# STM32.net
KiCad netlist of a schematic drawn in Altium Designer
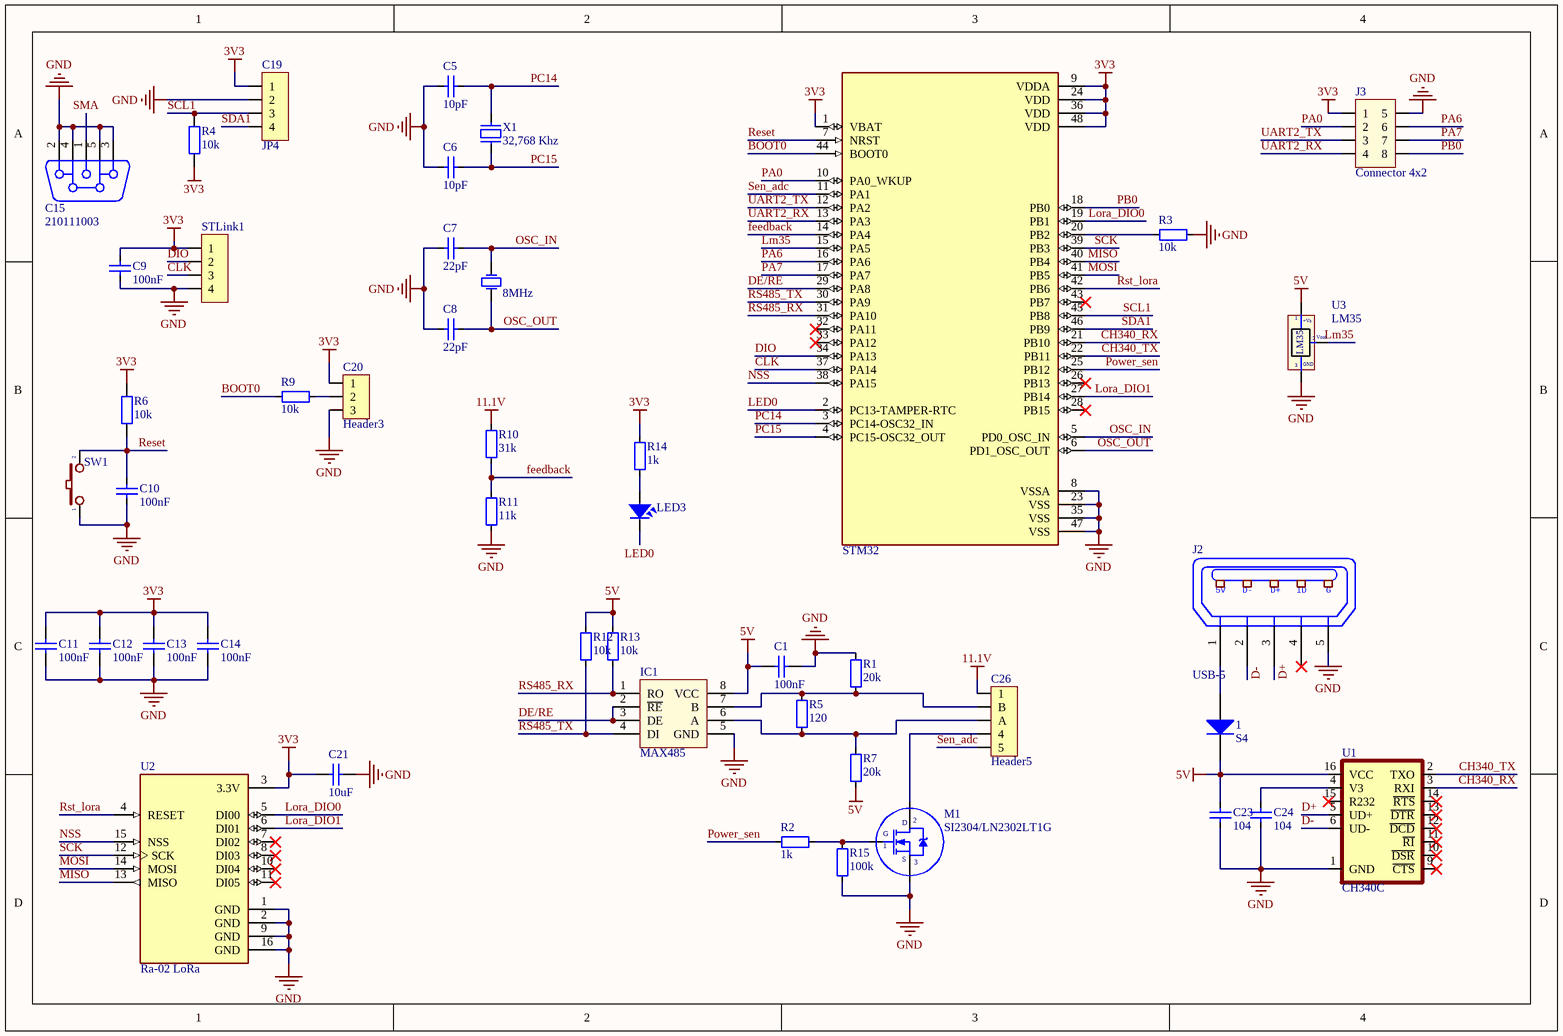
[diagram p0: STM32.SchDoc]

(export (version "E")
  (design (tool "Eeschema 10.0.6"))
  (components
    (comp (ref "1")
      (value "S4")
      (footprint "DIO-214AC(SMA)")
      (description "Dán")
      (libsource (lib "THU VIEN SCH") (part "Diode S4"))
    )
    (comp (ref "C1")
      (value "100nF")
      (footprint "CAP_0805")
      (description "Capacitor")
      (fields (field (name "PUBLISHER") "Altium Limited"))
      (libsource (lib "") (part "CapSMD_1"))
    )
    (comp (ref "C5")
      (value "10pF")
      (footprint "CAP_0805")
      (description "Capacitor")
      (fields (field (name "PUBLISHER") "Altium Limited"))
      (libsource (lib "My Library") (part "CapSMD"))
    )
    (comp (ref "C6")
      (value "10pF")
      (footprint "CAP_0805")
      (description "Capacitor")
      (fields (field (name "PUBLISHER") "Altium Limited"))
      (libsource (lib "My Library") (part "CapSMD"))
    )
    (comp (ref "C7")
      (value "22pF")
      (footprint "CAP_0805")
      (description "Capacitor")
      (fields (field (name "PUBLISHER") "Altium Limited"))
      (libsource (lib "My Library") (part "CapSMD"))
    )
    (comp (ref "C8")
      (value "22pF")
      (footprint "CAP_0805")
      (description "Capacitor")
      (fields (field (name "PUBLISHER") "Altium Limited"))
      (libsource (lib "My Library") (part "CapSMD"))
    )
    (comp (ref "C9")
      (value "100nF")
      (footprint "CAP_0805")
      (description "Capacitor")
      (fields (field (name "PUBLISHER") "Altium Limited"))
      (libsource (lib "My Library") (part "CapSMD"))
    )
    (comp (ref "C10")
      (value "100nF")
      (footprint "CAP_0805")
      (description "Capacitor")
      (fields (field (name "PUBLISHER") "Altium Limited"))
      (libsource (lib "My Library") (part "CapSMD"))
    )
    (comp (ref "C11")
      (value "100nF")
      (footprint "CAP_0805")
      (description "Capacitor")
      (fields (field (name "PUBLISHER") "Altium Limited"))
      (libsource (lib "") (part "CapSMD_1"))
    )
    (comp (ref "C12")
      (value "100nF")
      (footprint "CAP_0805")
      (description "Capacitor")
      (fields (field (name "PUBLISHER") "Altium Limited"))
      (libsource (lib "") (part "CapSMD_1"))
    )
    (comp (ref "C13")
      (value "100nF")
      (footprint "CAP_0805")
      (description "Capacitor")
      (fields (field (name "PUBLISHER") "Altium Limited"))
      (libsource (lib "") (part "CapSMD_1"))
    )
    (comp (ref "C14")
      (value "100nF")
      (footprint "CAP_0805")
      (description "Capacitor")
      (fields (field (name "PUBLISHER") "Altium Limited"))
      (libsource (lib "") (part "CapSMD_1"))
    )
    (comp (ref "C15")
      (value "210111003")
      (footprint "SMA-RA")
      (description "CONNECTOR ANTEN")
      (fields
        (field (name "MANUFACTURER") "Würth Elektronik eiSos GmbH")
        (field (name "CREATED BY") "Christin Zierenner")
      )
      (libsource (lib "My Library") (part "CON Ant"))
    )
    (comp (ref "C19")
      (value "JP4")
      (footprint "JP4-C1T")
      (description "WR-PHD 2.54 mm Angled Socket Header")
      (fields
        (field (name "MANUFACTURER") "Würth Elektronik eiSos GmbH")
        (field (name "PARTNO") "613004143121")
        (field (name "CREATED BY") "Karrer Zheng")
      )
      (libsource (lib "My Library") (part "JP4"))
    )
    (comp (ref "C20")
      (value "Header3")
      (footprint "JP3")
      (description "Header IDC, 3 x 1 Pin Vertical 2.54mm Pitch (Non-Boxed, Male)")
      (fields
        (field (name "MANUFACTURER") "Würth Elektronik eiSos GmbH")
        (field (name "PARTNO") "613002143121")
        (field (name "CREATED BY") "Karrer Zheng")
      )
      (libsource (lib "My Library") (part "Header3"))
    )
    (comp (ref "C21")
      (value "10uF")
      (footprint "CAP_0805")
      (description "Capacitor")
      (fields (field (name "PUBLISHER") "Altium Limited"))
      (libsource (lib "") (part "CapSMD_1"))
    )
    (comp (ref "C23")
      (value "104")
      (footprint "CAP_0805")
      (description "Capacitor")
      (fields (field (name "PUBLISHER") "Altium Limited"))
      (libsource (lib "My Library") (part "CapSMD"))
    )
    (comp (ref "C24")
      (value "104")
      (footprint "CAP_0805")
      (description "Capacitor")
      (fields (field (name "PUBLISHER") "Altium Limited"))
      (libsource (lib "My Library") (part "CapSMD"))
    )
    (comp (ref "C26")
      (value "Header5")
      (footprint "KF5-5")
      (description "Header IDC, 5 x 1 Pin Vertical 2.54mm Pitch (Non-Boxed, Male)")
      (fields
        (field (name "MANUFACTURER") "Würth Elektronik eiSos GmbH")
        (field (name "PARTNO") "613002143121")
        (field (name "CREATED BY") "Karrer Zheng")
      )
      (libsource (lib "My Library") (part "Header5"))
    )
    (comp (ref "IC1")
      (value "MAX485")
      (footprint "SO-8")
      (description "RS232 - RS485 (Same sn75176)")
      (libsource (lib "My Library") (part "MAX485"))
    )
    (comp (ref "J2")
      (value "USB-5")
      (footprint "USB-M1")
      (fields
        (field (name "MANUFACTURER") "FCI")
        (field (name "MANUFACTURER PART NUMBER") "10118193-0001LF")
        (field (name ".CREATOR") "MM")
        (field (name ".CHECKED PCB") "RF")
        (field (name ".CHECKED SCH") "MM")
      )
      (libsource (lib "My Library") (part "USB-5"))
    )
    (comp (ref "J3")
      (value "Connector 4x2")
      (footprint "JP4x2")
      (libsource (lib "My Library") (part "JP4x2"))
    )
    (comp (ref "LED3")
      (value "LED")
      (footprint "LED-0805-Blue")
      (description "LED Single colour Green and Red")
      (libsource (lib "My Library") (part "LED"))
    )
    (comp (ref "M1")
      (value "SI2304/LN2302LT1G")
      (footprint "SOT23A")
      (description "Generic N Channel MOSFET")
      (libsource (lib "My Library") (part "MOSFET_N"))
    )
    (comp (ref "R1")
      (value "20k")
      (footprint "RES-SMD-0805")
      (description "Resistor")
      (fields
        (field (name "MANUFACTURER") "Generic Components")
        (field (name "PUBLISHER") "Altium Hobart Technology Centre")
      )
      (libsource (lib "My Library") (part "Resistor - SMD"))
    )
    (comp (ref "R2")
      (value "1k")
      (footprint "RES-SMD-0805")
      (description "Resistor")
      (fields
        (field (name "MANUFACTURER") "Generic Components")
        (field (name "PUBLISHER") "Altium Hobart Technology Centre")
      )
      (libsource (lib "My Library") (part "Resistor - SMD"))
    )
    (comp (ref "R3")
      (value "10k")
      (footprint "RES-SMD-0805")
      (description "Resistor")
      (fields
        (field (name "MANUFACTURER") "Generic Components")
        (field (name "PUBLISHER") "Altium Hobart Technology Centre")
      )
      (libsource (lib "My Library") (part "Resistor - SMD"))
    )
    (comp (ref "R4")
      (value "10k")
      (footprint "RES_SMD_0805")
      (description "Resistor SMD")
      (fields
        (field (name "MANUFACTURER") "Generic Components")
        (field (name "PUBLISHER") "Altium Hobart Technology Centre")
      )
      (libsource (lib "") (part "Resistor - SMD_1"))
    )
    (comp (ref "R5")
      (value "120")
      (footprint "RES-SMD-0805")
      (description "Resistor")
      (fields
        (field (name "MANUFACTURER") "Generic Components")
        (field (name "PUBLISHER") "Altium Hobart Technology Centre")
      )
      (libsource (lib "My Library") (part "Resistor - SMD"))
    )
    (comp (ref "R6")
      (value "10k")
      (footprint "RES_SMD_0805")
      (description "Resistor SMD")
      (fields
        (field (name "MANUFACTURER") "Generic Components")
        (field (name "PUBLISHER") "Altium Hobart Technology Centre")
      )
      (libsource (lib "") (part "Resistor - SMD_1"))
    )
    (comp (ref "R7")
      (value "20k")
      (footprint "RES-SMD-0805")
      (description "Resistor")
      (fields
        (field (name "MANUFACTURER") "Generic Components")
        (field (name "PUBLISHER") "Altium Hobart Technology Centre")
      )
      (libsource (lib "My Library") (part "Resistor - SMD"))
    )
    (comp (ref "R9")
      (value "10k")
      (footprint "RES-SMD-0805")
      (description "Resistor")
      (fields
        (field (name "MANUFACTURER") "Generic Components")
        (field (name "PUBLISHER") "Altium Hobart Technology Centre")
      )
      (libsource (lib "My Library") (part "Resistor - SMD"))
    )
    (comp (ref "R10")
      (value "31k")
      (footprint "RES-SMD-0805")
      (description "Resistor")
      (fields
        (field (name "MANUFACTURER") "Generic Components")
        (field (name "PUBLISHER") "Altium Hobart Technology Centre")
      )
      (libsource (lib "My Library") (part "Resistor - SMD"))
    )
    (comp (ref "R11")
      (value "11k")
      (footprint "RES-SMD-0805")
      (description "Resistor")
      (fields
        (field (name "MANUFACTURER") "Generic Components")
        (field (name "PUBLISHER") "Altium Hobart Technology Centre")
      )
      (libsource (lib "My Library") (part "Resistor - SMD"))
    )
    (comp (ref "R12")
      (value "10k")
      (footprint "RES-SMD-0805")
      (description "Resistor")
      (fields
        (field (name "MANUFACTURER") "Generic Components")
        (field (name "PUBLISHER") "Altium Hobart Technology Centre")
      )
      (libsource (lib "My Library") (part "Resistor - SMD"))
    )
    (comp (ref "R13")
      (value "10k")
      (footprint "RES-SMD-0805")
      (description "Resistor")
      (fields
        (field (name "MANUFACTURER") "Generic Components")
        (field (name "PUBLISHER") "Altium Hobart Technology Centre")
      )
      (libsource (lib "My Library") (part "Resistor - SMD"))
    )
    (comp (ref "R14")
      (value "1k")
      (footprint "RES-SMD-0805")
      (description "Resistor")
      (fields
        (field (name "MANUFACTURER") "Generic Components")
        (field (name "PUBLISHER") "Altium Hobart Technology Centre")
      )
      (libsource (lib "My Library") (part "Resistor - SMD"))
    )
    (comp (ref "R15")
      (value "100k")
      (footprint "RES-SMD-0805")
      (description "Resistor")
      (fields
        (field (name "MANUFACTURER") "Generic Components")
        (field (name "PUBLISHER") "Altium Hobart Technology Centre")
      )
      (libsource (lib "My Library") (part "Resistor - SMD"))
    )
    (comp (ref "STLink1")
      (value "JP4")
      (footprint "JP4-C1T")
      (description "WR-PHD 2.54 mm Angled Socket Header")
      (fields
        (field (name "MANUFACTURER") "Würth Elektronik eiSos GmbH")
        (field (name "PARTNO") "613004143121")
        (field (name "CREATED BY") "Karrer Zheng")
      )
      (libsource (lib "My Library") (part "JP4"))
    )
    (comp (ref "STM32")
      (value "STM32")
      (footprint "LQFP 48")
      (description "STM32 ARM-based 32-bit MCU with 64 Kbytes Flash, 64-pin LQFP, Industrial Temperature")
      (libsource (lib "My Library") (part "STM32F103C8T6"))
    )
    (comp (ref "SW1")
      (value "SW")
      (footprint "SW2")
      (description "Switch button 2 pin")
      (libsource (lib "My Library") (part "SW2"))
    )
    (comp (ref "U1")
      (value "CH340C")
      (footprint "SOP-16")
      (description "USB to serial chip CH340")
      (fields (field (name "MF") "WCH"))
      (libsource (lib "My Library") (part "CH340C"))
    )
    (comp (ref "U2")
      (value "Ra-02 LoRa")
      (footprint "Ra-02")
      (description "LoRa Module Ra-02")
      (libsource (lib "My Library") (part "Ra-02 LoRa"))
    )
    (comp (ref "U3")
      (value "LM35")
      (footprint "QTO-92")
      (description "Teminal")
      (libsource (lib "My Library") (part "LM35"))
    )
    (comp (ref "X1")
      (value "32,768 Khz")
      (footprint "32k_SMD")
      (description "Crystal 32,768kHz for timer real")
      (libsource (lib "My Library") (part "XT32k"))
    )
    (comp (ref "Y1")
      (value "8MHz")
      (footprint "XTAL")
      (description "Crystal Oscillator")
      (fields (field (name "PUBLISHER") "Altium Limited"))
      (libsource (lib "My Library") (part "XTAL"))
    )
  )
  (nets
    (net (code "1") (name "/BOOT0") (class "Default")
      (node (ref "R9") (pin "2") (pinfunction "2_2") (pintype "passive"))
      (node (ref "STM32") (pin "44") (pinfunction "BOOT0_44") (pintype "input"))
    )
    (net (code "2") (name "/CH340_RX") (class "Default")
      (node (ref "STM32") (pin "21") (pinfunction "PB10_21") (pintype "bidirectional"))
      (node (ref "U1") (pin "3") (pinfunction "RXI_3") (pintype "bidirectional"))
    )
    (net (code "3") (name "/CH340_TX") (class "Default")
      (node (ref "STM32") (pin "22") (pinfunction "PB11_22") (pintype "bidirectional"))
      (node (ref "U1") (pin "2") (pinfunction "TXO_2") (pintype "bidirectional"))
    )
    (net (code "4") (name "/CLK") (class "Default")
      (node (ref "STLink1") (pin "3") (pinfunction "3_3") (pintype "passive"))
      (node (ref "STM32") (pin "37") (pinfunction "PA14_37") (pintype "bidirectional"))
    )
    (net (code "5") (name "/D+") (class "Default")
      (node (ref "J2") (pin "3") (pinfunction "P3_3") (pintype "passive"))
      (node (ref "U1") (pin "5") (pinfunction "UD+_5") (pintype "bidirectional"))
    )
    (net (code "6") (name "/D-") (class "Default")
      (node (ref "J2") (pin "2") (pinfunction "P2_2") (pintype "passive"))
      (node (ref "U1") (pin "6") (pinfunction "UD-_6") (pintype "bidirectional"))
    )
    (net (code "7") (name "/DE{slash}RE") (class "Default")
      (node (ref "IC1") (pin "2") (pinfunction "~{RE}_2") (pintype "passive"))
      (node (ref "IC1") (pin "3") (pinfunction "DE_3") (pintype "passive"))
      (node (ref "STM32") (pin "29") (pinfunction "PA8_29") (pintype "bidirectional"))
    )
    (net (code "8") (name "/DIO") (class "Default")
      (node (ref "STLink1") (pin "2") (pinfunction "2_2") (pintype "passive"))
      (node (ref "STM32") (pin "34") (pinfunction "PA13_34") (pintype "bidirectional"))
    )
    (net (code "9") (name "/LED0") (class "Default")
      (node (ref "LED3") (pin "2") (pinfunction "2_2") (pintype "passive"))
      (node (ref "STM32") (pin "2") (pinfunction "PC13-TAMPER-RTC_2") (pintype "bidirectional"))
    )
    (net (code "10") (name "/Lm35") (class "Default")
      (node (ref "STM32") (pin "15") (pinfunction "PA5_15") (pintype "bidirectional"))
      (node (ref "U3") (pin "2") (pinfunction "Vout_2") (pintype "passive"))
    )
    (net (code "11") (name "/Lora_DIO0") (class "Default")
      (node (ref "STM32") (pin "19") (pinfunction "PB1_19") (pintype "bidirectional"))
      (node (ref "U2") (pin "5") (pinfunction "DI00_5") (pintype "bidirectional"))
    )
    (net (code "12") (name "/Lora_DIO1") (class "Default")
      (node (ref "STM32") (pin "27") (pinfunction "PB14_27") (pintype "bidirectional"))
      (node (ref "U2") (pin "6") (pinfunction "DI01_6") (pintype "bidirectional"))
    )
    (net (code "13") (name "/MISO") (class "Default")
      (node (ref "STM32") (pin "40") (pinfunction "PB4_40") (pintype "bidirectional"))
      (node (ref "U2") (pin "13") (pinfunction "MISO_13") (pintype "output"))
    )
    (net (code "14") (name "/MOSI") (class "Default")
      (node (ref "STM32") (pin "41") (pinfunction "PB5_41") (pintype "bidirectional"))
      (node (ref "U2") (pin "14") (pinfunction "MOSI_14") (pintype "input"))
    )
    (net (code "15") (name "/NSS") (class "Default")
      (node (ref "STM32") (pin "38") (pinfunction "PA15_38") (pintype "bidirectional"))
      (node (ref "U2") (pin "15") (pinfunction "NSS_15") (pintype "input"))
    )
    (net (code "16") (name "/OSC_IN") (class "Default")
      (node (ref "C7") (pin "1") (pinfunction "1_1") (pintype "passive"))
      (node (ref "STM32") (pin "5") (pinfunction "PD0_OSC_IN_5") (pintype "bidirectional"))
      (node (ref "Y1") (pin "2") (pinfunction "OSC2_2") (pintype "passive"))
    )
    (net (code "17") (name "/OSC_OUT") (class "Default")
      (node (ref "C8") (pin "1") (pinfunction "1_1") (pintype "passive"))
      (node (ref "STM32") (pin "6") (pinfunction "PD1_OSC_OUT_6") (pintype "bidirectional"))
      (node (ref "Y1") (pin "1") (pinfunction "OSC1_1") (pintype "passive"))
    )
    (net (code "18") (name "/PA0") (class "Default")
      (node (ref "J3") (pin "2") (pinfunction "2_2") (pintype "passive"))
      (node (ref "STM32") (pin "10") (pinfunction "PA0_WKUP_10") (pintype "bidirectional"))
    )
    (net (code "19") (name "/PA6") (class "Default")
      (node (ref "J3") (pin "6") (pinfunction "6_6") (pintype "passive"))
      (node (ref "STM32") (pin "16") (pinfunction "PA6_16") (pintype "bidirectional"))
    )
    (net (code "20") (name "/PA7") (class "Default")
      (node (ref "J3") (pin "7") (pinfunction "7_7") (pintype "passive"))
      (node (ref "STM32") (pin "17") (pinfunction "PA7_17") (pintype "bidirectional"))
    )
    (net (code "21") (name "/PB0") (class "Default")
      (node (ref "J3") (pin "8") (pinfunction "8_8") (pintype "passive"))
      (node (ref "STM32") (pin "18") (pinfunction "PB0_18") (pintype "bidirectional"))
    )
    (net (code "22") (name "/PC14") (class "Default")
      (node (ref "C5") (pin "1") (pinfunction "1_1") (pintype "passive"))
      (node (ref "STM32") (pin "3") (pinfunction "PC14-OSC32_IN_3") (pintype "bidirectional"))
      (node (ref "X1") (pin "1") (pinfunction "1_1") (pintype "passive"))
    )
    (net (code "23") (name "/PC15") (class "Default")
      (node (ref "C6") (pin "1") (pinfunction "1_1") (pintype "passive"))
      (node (ref "STM32") (pin "4") (pinfunction "PC15-OSC32_OUT_4") (pintype "bidirectional"))
      (node (ref "X1") (pin "2") (pinfunction "2_2") (pintype "passive"))
    )
    (net (code "24") (name "/Power_sen") (class "Default")
      (node (ref "R2") (pin "1") (pinfunction "1_1") (pintype "passive"))
      (node (ref "STM32") (pin "25") (pinfunction "PB12_25") (pintype "bidirectional"))
    )
    (net (code "25") (name "/RS485_RX") (class "Default")
      (node (ref "IC1") (pin "1") (pinfunction "RO_1") (pintype "passive"))
      (node (ref "R13") (pin "2") (pinfunction "2_2") (pintype "passive"))
      (node (ref "STM32") (pin "31") (pinfunction "PA10_31") (pintype "bidirectional"))
    )
    (net (code "26") (name "/RS485_TX") (class "Default")
      (node (ref "IC1") (pin "4") (pinfunction "DI_4") (pintype "passive"))
      (node (ref "R12") (pin "2") (pinfunction "2_2") (pintype "passive"))
      (node (ref "STM32") (pin "30") (pinfunction "PA9_30") (pintype "bidirectional"))
    )
    (net (code "27") (name "/Reset") (class "Default")
      (node (ref "C10") (pin "1") (pinfunction "1_1") (pintype "passive"))
      (node (ref "R6") (pin "2") (pinfunction "2_2") (pintype "passive"))
      (node (ref "STM32") (pin "7") (pinfunction "NRST_7") (pintype "input"))
      (node (ref "SW1") (pin "2") (pinfunction "2_2") (pintype "passive"))
    )
    (net (code "28") (name "/Rst_lora") (class "Default")
      (node (ref "STM32") (pin "42") (pinfunction "PB6_42") (pintype "bidirectional"))
      (node (ref "U2") (pin "4") (pinfunction "RESET_4") (pintype "input"))
    )
    (net (code "29") (name "/SCK") (class "Default")
      (node (ref "STM32") (pin "39") (pinfunction "PB3_39") (pintype "bidirectional"))
      (node (ref "U2") (pin "12") (pinfunction "SCK_12") (pintype "input"))
    )
    (net (code "30") (name "/SCL1") (class "Default")
      (node (ref "C19") (pin "3") (pinfunction "3_3") (pintype "passive"))
      (node (ref "R4") (pin "2") (pinfunction "2_2") (pintype "passive"))
      (node (ref "STM32") (pin "45") (pinfunction "PB8_45") (pintype "bidirectional"))
    )
    (net (code "31") (name "/SDA1") (class "Default")
      (node (ref "C19") (pin "4") (pinfunction "4_4") (pintype "passive"))
      (node (ref "STM32") (pin "46") (pinfunction "PB9_46") (pintype "bidirectional"))
    )
    (net (code "32") (name "/SMA") (class "Default")
      (node (ref "C15") (pin "1") (pinfunction "1_1") (pintype "passive"))
    )
    (net (code "33") (name "/Sen_adc") (class "Default")
      (node (ref "C26") (pin "5") (pinfunction "5_5") (pintype "passive"))
      (node (ref "STM32") (pin "11") (pinfunction "PA1_11") (pintype "bidirectional"))
    )
    (net (code "34") (name "/UART2_RX") (class "Default")
      (node (ref "J3") (pin "4") (pinfunction "4_4") (pintype "passive"))
      (node (ref "STM32") (pin "13") (pinfunction "PA3_13") (pintype "bidirectional"))
    )
    (net (code "35") (name "/UART2_TX") (class "Default")
      (node (ref "J3") (pin "3") (pinfunction "3_3") (pintype "passive"))
      (node (ref "STM32") (pin "12") (pinfunction "PA2_12") (pintype "bidirectional"))
    )
    (net (code "36") (name "/feedback") (class "Default")
      (node (ref "R10") (pin "2") (pinfunction "2_2") (pintype "passive"))
      (node (ref "R11") (pin "1") (pinfunction "1_1") (pintype "passive"))
      (node (ref "STM32") (pin "14") (pinfunction "PA4_14") (pintype "bidirectional"))
    )
    (net (code "37") (name "3V3") (class "Default")
      (node (ref "C11") (pin "1") (pinfunction "1_1") (pintype "passive"))
      (node (ref "C12") (pin "1") (pinfunction "1_1") (pintype "passive"))
      (node (ref "C13") (pin "1") (pinfunction "1_1") (pintype "passive"))
      (node (ref "C14") (pin "1") (pinfunction "1_1") (pintype "passive"))
      (node (ref "C19") (pin "1") (pinfunction "1_1") (pintype "passive"))
      (node (ref "C20") (pin "1") (pinfunction "1_1") (pintype "passive"))
      (node (ref "C21") (pin "1") (pinfunction "1_1") (pintype "passive"))
      (node (ref "C9") (pin "1") (pinfunction "1_1") (pintype "passive"))
      (node (ref "J3") (pin "1") (pinfunction "1_1") (pintype "passive"))
      (node (ref "R14") (pin "1") (pinfunction "1_1") (pintype "passive"))
      (node (ref "R4") (pin "1") (pinfunction "1_1") (pintype "passive"))
      (node (ref "R6") (pin "1") (pinfunction "1_1") (pintype "passive"))
      (node (ref "STLink1") (pin "1") (pinfunction "1_1") (pintype "passive"))
      (node (ref "STM32") (pin "1") (pinfunction "VBAT_1") (pintype "bidirectional"))
      (node (ref "STM32") (pin "24") (pinfunction "VDD_24") (pintype "power_in"))
      (node (ref "STM32") (pin "36") (pinfunction "VDD_36") (pintype "power_in"))
      (node (ref "STM32") (pin "48") (pinfunction "VDD_48") (pintype "power_in"))
      (node (ref "STM32") (pin "9") (pinfunction "VDDA_9") (pintype "power_in"))
      (node (ref "U2") (pin "3") (pinfunction "3.3V_3") (pintype "power_in"))
    )
    (net (code "38") (name "5V") (class "Default")
      (node (ref "1") (pin "2") (pinfunction "K_2") (pintype "passive"))
      (node (ref "C1") (pin "1") (pinfunction "1_1") (pintype "passive"))
      (node (ref "C23") (pin "2") (pinfunction "2_2") (pintype "passive"))
      (node (ref "IC1") (pin "8") (pinfunction "VCC_8") (pintype "passive"))
      (node (ref "R12") (pin "1") (pinfunction "1_1") (pintype "passive"))
      (node (ref "R13") (pin "1") (pinfunction "1_1") (pintype "passive"))
      (node (ref "R7") (pin "2") (pinfunction "2_2") (pintype "passive"))
      (node (ref "U1") (pin "16") (pinfunction "VCC_16") (pintype "bidirectional"))
      (node (ref "U3") (pin "1") (pinfunction "+Vs_1") (pintype "passive"))
    )
    (net (code "39") (name "11.1V") (class "Default")
      (node (ref "C26") (pin "1") (pinfunction "1_1") (pintype "passive"))
      (node (ref "R10") (pin "1") (pinfunction "1_1") (pintype "passive"))
    )
    (net (code "40") (name "GND") (class "Default")
      (node (ref "C1") (pin "2") (pinfunction "2_2") (pintype "passive"))
      (node (ref "C10") (pin "2") (pinfunction "2_2") (pintype "passive"))
      (node (ref "C11") (pin "2") (pinfunction "2_2") (pintype "passive"))
      (node (ref "C12") (pin "2") (pinfunction "2_2") (pintype "passive"))
      (node (ref "C13") (pin "2") (pinfunction "2_2") (pintype "passive"))
      (node (ref "C14") (pin "2") (pinfunction "2_2") (pintype "passive"))
      (node (ref "C15") (pin "2") (pinfunction "2_2") (pintype "passive"))
      (node (ref "C15") (pin "3") (pinfunction "3_3") (pintype "passive"))
      (node (ref "C15") (pin "4") (pinfunction "4_4") (pintype "passive"))
      (node (ref "C15") (pin "5") (pinfunction "5_5") (pintype "passive"))
      (node (ref "C19") (pin "2") (pinfunction "2_2") (pintype "passive"))
      (node (ref "C20") (pin "3") (pinfunction "3_3") (pintype "passive"))
      (node (ref "C21") (pin "2") (pinfunction "2_2") (pintype "passive"))
      (node (ref "C23") (pin "1") (pinfunction "1_1") (pintype "passive"))
      (node (ref "C24") (pin "1") (pinfunction "1_1") (pintype "passive"))
      (node (ref "C5") (pin "2") (pinfunction "2_2") (pintype "passive"))
      (node (ref "C6") (pin "2") (pinfunction "2_2") (pintype "passive"))
      (node (ref "C7") (pin "2") (pinfunction "2_2") (pintype "passive"))
      (node (ref "C8") (pin "2") (pinfunction "2_2") (pintype "passive"))
      (node (ref "C9") (pin "2") (pinfunction "2_2") (pintype "passive"))
      (node (ref "IC1") (pin "5") (pinfunction "GND_5") (pintype "passive"))
      (node (ref "J2") (pin "5") (pinfunction "P5_5") (pintype "passive"))
      (node (ref "J3") (pin "5") (pinfunction "5_5") (pintype "passive"))
      (node (ref "M1") (pin "3") (pinfunction "S_3") (pintype "passive"))
      (node (ref "R1") (pin "1") (pinfunction "1_1") (pintype "passive"))
      (node (ref "R11") (pin "2") (pinfunction "2_2") (pintype "passive"))
      (node (ref "R15") (pin "1") (pinfunction "1_1") (pintype "passive"))
      (node (ref "R3") (pin "1") (pinfunction "1_1") (pintype "passive"))
      (node (ref "STLink1") (pin "4") (pinfunction "4_4") (pintype "passive"))
      (node (ref "STM32") (pin "23") (pinfunction "VSS_23") (pintype "power_in"))
      (node (ref "STM32") (pin "35") (pinfunction "VSS_35") (pintype "power_in"))
      (node (ref "STM32") (pin "47") (pinfunction "VSS_47") (pintype "power_in"))
      (node (ref "STM32") (pin "8") (pinfunction "VSSA_8") (pintype "power_in"))
      (node (ref "SW1") (pin "1") (pinfunction "1_1") (pintype "passive"))
      (node (ref "U1") (pin "1") (pinfunction "GND_1") (pintype "bidirectional"))
      (node (ref "U2") (pin "1") (pinfunction "GND_1") (pintype "power_in"))
      (node (ref "U2") (pin "16") (pinfunction "GND_16") (pintype "power_in"))
      (node (ref "U2") (pin "2") (pinfunction "GND_2") (pintype "power_in"))
      (node (ref "U2") (pin "9") (pinfunction "GND_9") (pintype "power_in"))
      (node (ref "U3") (pin "3") (pinfunction "-_3") (pintype "passive"))
    )
    (net (code "41") (name "Net-(1-A)") (class "Default")
      (node (ref "1") (pin "1") (pinfunction "A_1") (pintype "passive"))
      (node (ref "J2") (pin "1") (pinfunction "P1_1") (pintype "passive"))
    )
    (net (code "42") (name "Net-(C20-Pad2)") (class "Default")
      (node (ref "C20") (pin "2") (pinfunction "2_2") (pintype "passive"))
      (node (ref "R9") (pin "1") (pinfunction "1_1") (pintype "passive"))
    )
    (net (code "43") (name "Net-(C26-A)") (class "Default")
      (node (ref "C26") (pin "3") (pinfunction "A_3") (pintype "passive"))
      (node (ref "IC1") (pin "6") (pinfunction "A_6") (pintype "passive"))
      (node (ref "R5") (pin "2") (pinfunction "2_2") (pintype "passive"))
      (node (ref "R7") (pin "1") (pinfunction "1_1") (pintype "passive"))
    )
    (net (code "44") (name "Net-(C26-B)") (class "Default")
      (node (ref "C26") (pin "2") (pinfunction "B_2") (pintype "passive"))
      (node (ref "IC1") (pin "7") (pinfunction "B_7") (pintype "passive"))
      (node (ref "R1") (pin "2") (pinfunction "2_2") (pintype "passive"))
      (node (ref "R5") (pin "1") (pinfunction "1_1") (pintype "passive"))
    )
    (net (code "45") (name "Net-(LED3-Pad1)") (class "Default")
      (node (ref "LED3") (pin "1") (pinfunction "1_1") (pintype "passive"))
      (node (ref "R14") (pin "2") (pinfunction "2_2") (pintype "passive"))
    )
    (net (code "46") (name "Net-(M1-D)") (class "Default")
      (node (ref "C26") (pin "4") (pinfunction "4_4") (pintype "passive"))
      (node (ref "M1") (pin "2") (pinfunction "D_2") (pintype "passive"))
    )
    (net (code "47") (name "Net-(M1-G)") (class "Default")
      (node (ref "M1") (pin "1") (pinfunction "G_1") (pintype "passive"))
      (node (ref "R15") (pin "2") (pinfunction "2_2") (pintype "passive"))
      (node (ref "R2") (pin "2") (pinfunction "2_2") (pintype "passive"))
    )
    (net (code "48") (name "Net-(STM32-PB2)") (class "Default")
      (node (ref "R3") (pin "2") (pinfunction "2_2") (pintype "passive"))
      (node (ref "STM32") (pin "20") (pinfunction "PB2_20") (pintype "bidirectional"))
    )
    (net (code "49") (name "Net-(U1-V3)") (class "Default")
      (node (ref "C24") (pin "2") (pinfunction "2_2") (pintype "passive"))
      (node (ref "U1") (pin "4") (pinfunction "V3_4") (pintype "bidirectional"))
    )
    (net (code "50") (name "unconnected-(J2-P4-Pad4)") (class "Default")
      (node (ref "J2") (pin "4") (pinfunction "P4_4") (pintype "passive+no_connect"))
    )
    (net (code "51") (name "unconnected-(STM32-PA11-Pad32)") (class "Default")
      (node (ref "STM32") (pin "32") (pinfunction "PA11_32") (pintype "bidirectional+no_connect"))
    )
    (net (code "52") (name "unconnected-(STM32-PA12-Pad33)") (class "Default")
      (node (ref "STM32") (pin "33") (pinfunction "PA12_33") (pintype "bidirectional+no_connect"))
    )
    (net (code "53") (name "unconnected-(STM32-PB7-Pad43)") (class "Default")
      (node (ref "STM32") (pin "43") (pinfunction "PB7_43") (pintype "bidirectional+no_connect"))
    )
    (net (code "54") (name "unconnected-(STM32-PB13-Pad26)") (class "Default")
      (node (ref "STM32") (pin "26") (pinfunction "PB13_26") (pintype "bidirectional+no_connect"))
    )
    (net (code "55") (name "unconnected-(STM32-PB15-Pad28)") (class "Default")
      (node (ref "STM32") (pin "28") (pinfunction "PB15_28") (pintype "bidirectional+no_connect"))
    )
    (net (code "56") (name "unconnected-(U1-R232-Pad15)") (class "Default")
      (node (ref "U1") (pin "15") (pinfunction "R232_15") (pintype "bidirectional+no_connect"))
    )
    (net (code "57") (name "unconnected-(U1-~{CTS}-Pad9)") (class "Default")
      (node (ref "U1") (pin "9") (pinfunction "~{CTS}_9") (pintype "bidirectional+no_connect"))
    )
    (net (code "58") (name "unconnected-(U1-~{DCD}-Pad12)") (class "Default")
      (node (ref "U1") (pin "12") (pinfunction "~{DCD}_12") (pintype "bidirectional+no_connect"))
    )
    (net (code "59") (name "unconnected-(U1-~{DSR}-Pad10)") (class "Default")
      (node (ref "U1") (pin "10") (pinfunction "~{DSR}_10") (pintype "bidirectional+no_connect"))
    )
    (net (code "60") (name "unconnected-(U1-~{DTR}-Pad13)") (class "Default")
      (node (ref "U1") (pin "13") (pinfunction "~{DTR}_13") (pintype "bidirectional+no_connect"))
    )
    (net (code "61") (name "unconnected-(U1-~{RI}-Pad11)") (class "Default")
      (node (ref "U1") (pin "11") (pinfunction "~{RI}_11") (pintype "bidirectional+no_connect"))
    )
    (net (code "62") (name "unconnected-(U1-~{RTS}-Pad14)") (class "Default")
      (node (ref "U1") (pin "14") (pinfunction "~{RTS}_14") (pintype "bidirectional+no_connect"))
    )
    (net (code "63") (name "unconnected-(U2-DI02-Pad7)") (class "Default")
      (node (ref "U2") (pin "7") (pinfunction "DI02_7") (pintype "bidirectional+no_connect"))
    )
    (net (code "64") (name "unconnected-(U2-DI03-Pad8)") (class "Default")
      (node (ref "U2") (pin "8") (pinfunction "DI03_8") (pintype "bidirectional+no_connect"))
    )
    (net (code "65") (name "unconnected-(U2-DI04-Pad10)") (class "Default")
      (node (ref "U2") (pin "10") (pinfunction "DI04_10") (pintype "bidirectional+no_connect"))
    )
    (net (code "66") (name "unconnected-(U2-DI05-Pad11)") (class "Default")
      (node (ref "U2") (pin "11") (pinfunction "DI05_11") (pintype "bidirectional+no_connect"))
    )
  )
)
